# SCH_555_timer_compact_2022-07-11.net
KiCad netlist of a schematic drawn in EasyEDA
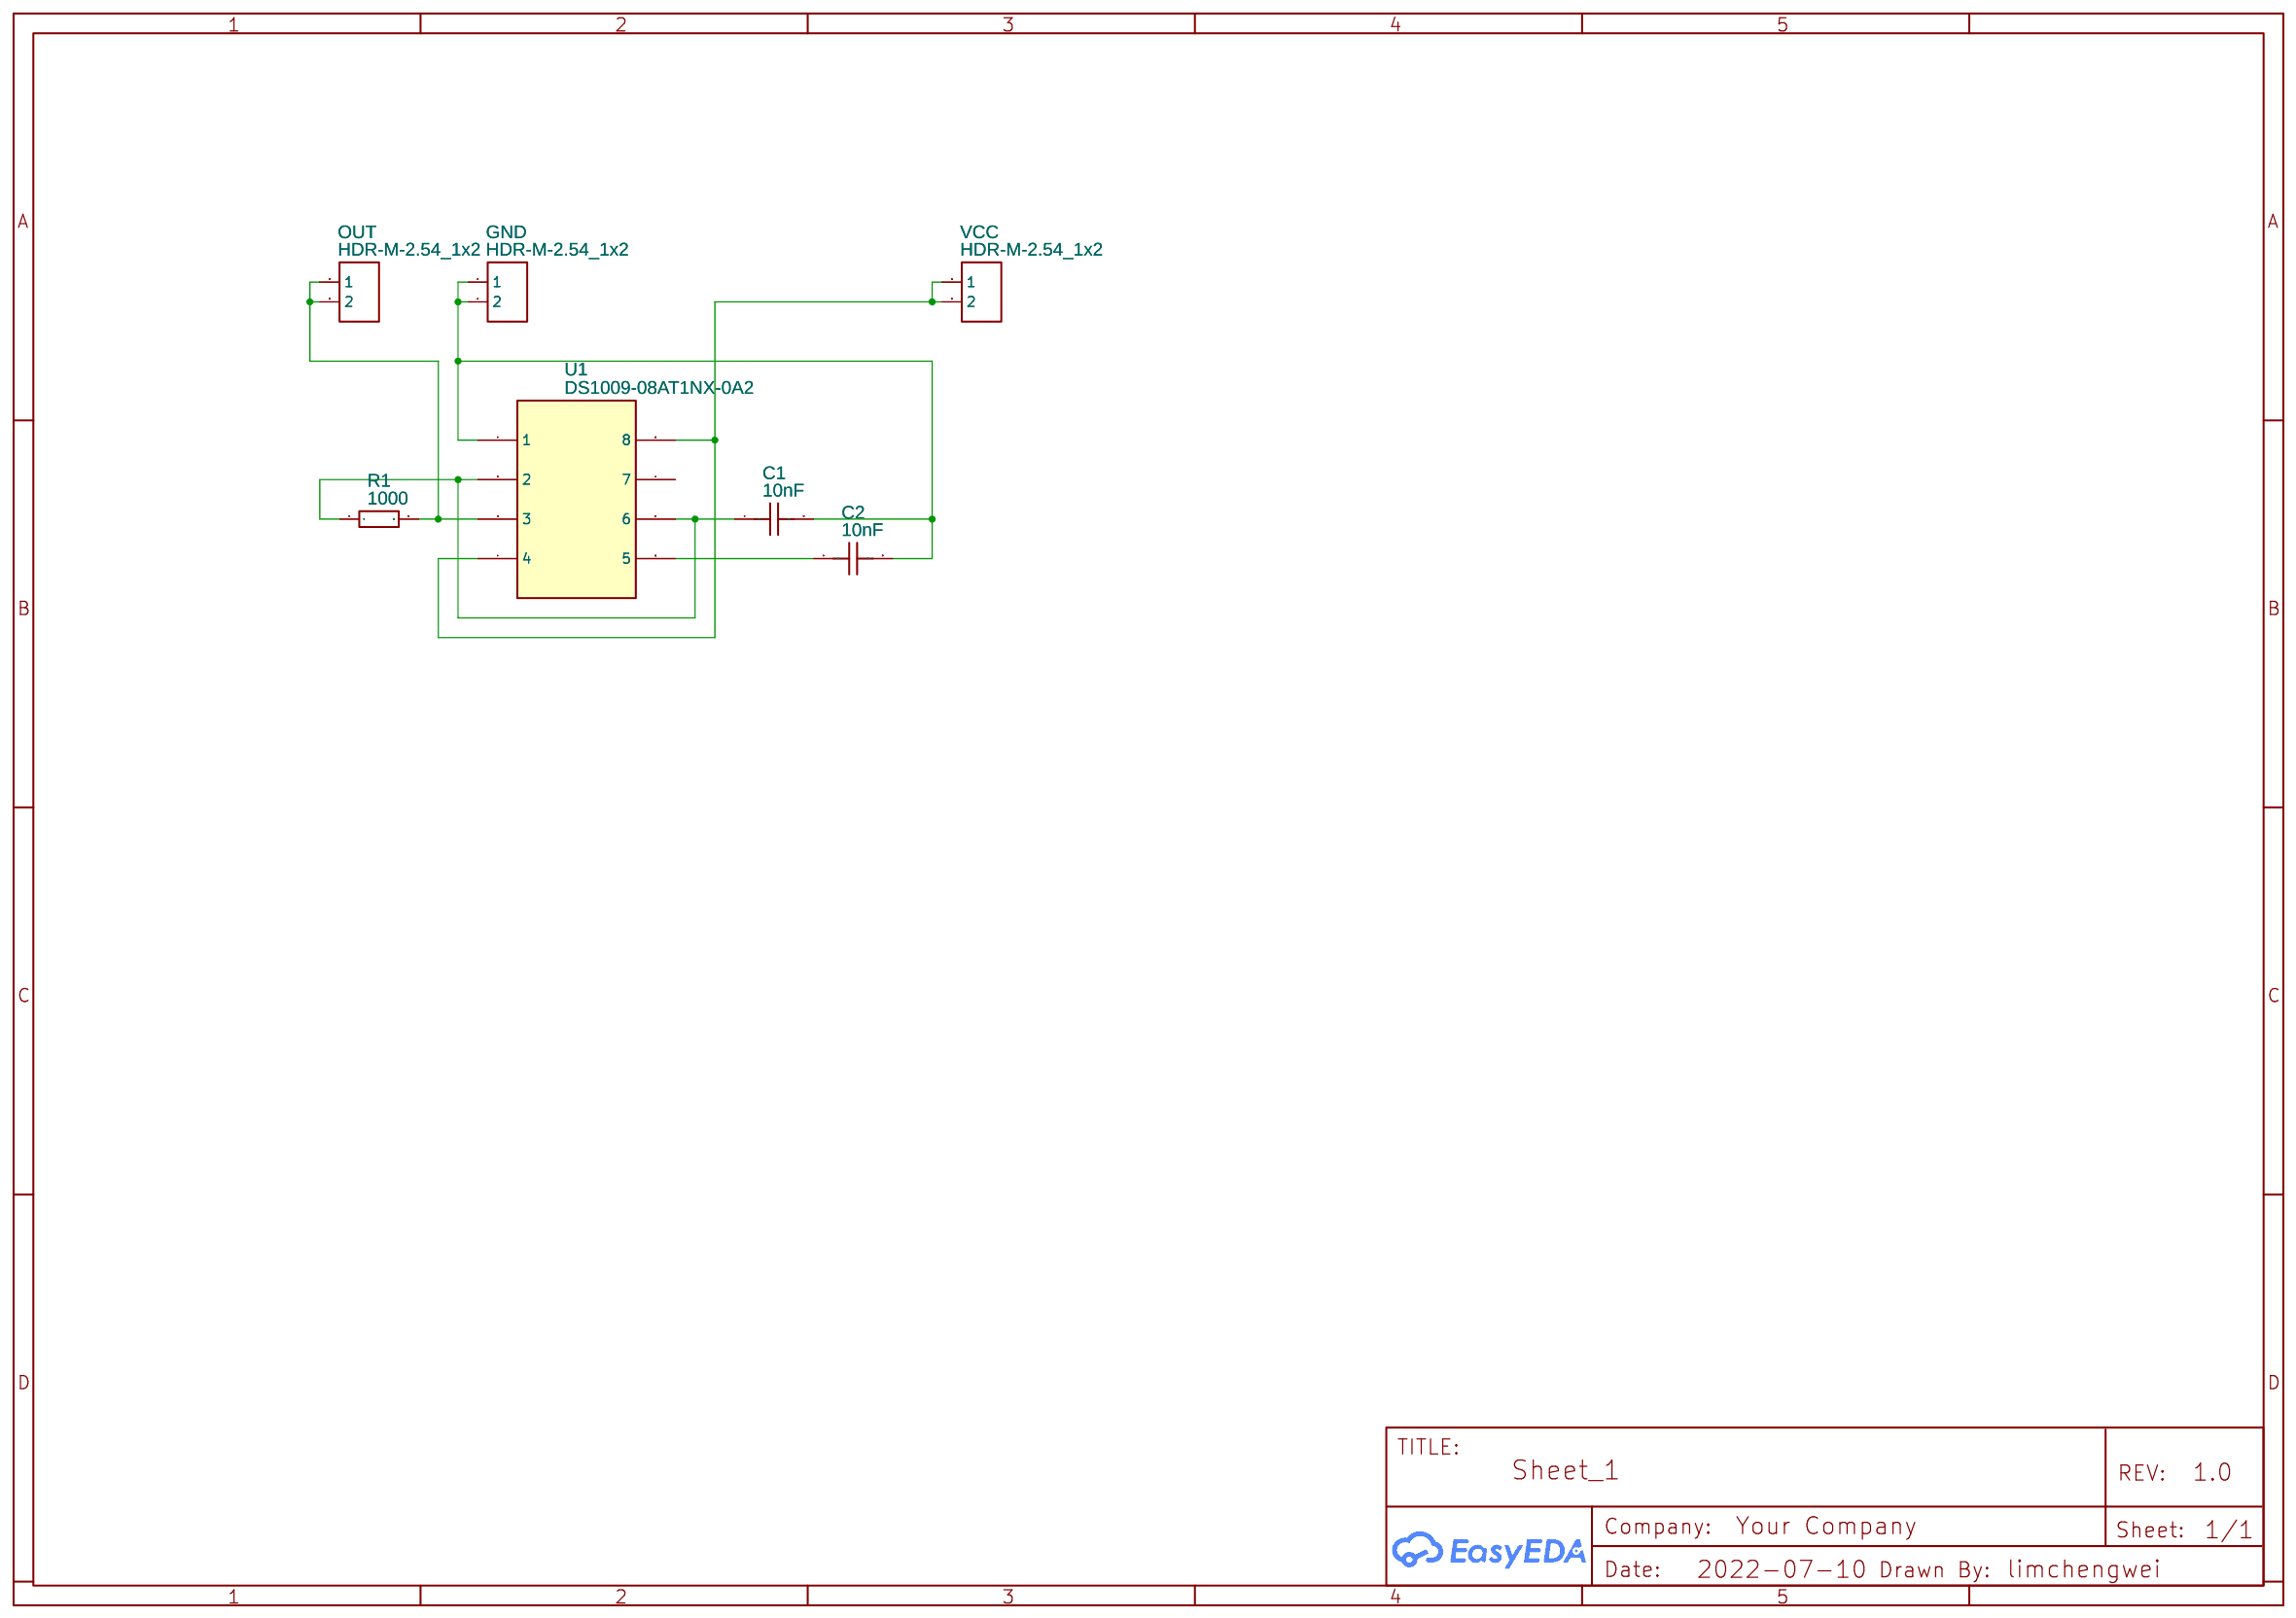
[diagram p0: schematic sheet]

(export (version "E")
  (design (tool "Eeschema 10.0.6"))
  (components
    (comp (ref "C1")
      (value "10nF")
      (fields
        (field (name "BOM_Manufacturer Part") "CC1H103MC76DB45A30S8")
        (field (name "BOM_Supplier Part") "C377837")
      )
      (libsource (lib "") (part "CC1H103MC76DB45A30S8"))
    )
    (comp (ref "C2")
      (value "10nF")
      (fields
        (field (name "BOM_Manufacturer Part") "CC1H103MC76DB45A30S8")
        (field (name "BOM_Supplier Part") "C377837")
      )
      (libsource (lib "") (part "CC1H103MC76DB45A30S8"))
    )
    (comp (ref "GND")
      (value "HDR-M-2.54_1x2")
      (fields (field (name "BOM_Supplier Part") "C124375"))
      (libsource (lib "") (part "HDR-M-2.54_1x2_2"))
    )
    (comp (ref "OUT")
      (value "HDR-M-2.54_1x2")
      (fields (field (name "BOM_Supplier Part") "C124375"))
      (libsource (lib "") (part "HDR-M-2.54_1x2_1"))
    )
    (comp (ref "R1")
      (value "1000")
      (fields (field (name "BOM_Supplier Part") "C119312"))
      (libsource (lib "") (part "MF1/4W-300Ω±1% T52"))
    )
    (comp (ref "U1")
      (value "DS1009-08AT1NX-0A2")
      (fields (field (name "BOM_Supplier Part") "C72124"))
      (libsource (lib "") (part "DS1009-08AT1NX-0A2"))
    )
    (comp (ref "VCC")
      (value "HDR-M-2.54_1x2")
      (fields (field (name "BOM_Supplier Part") "C124375"))
      (libsource (lib "") (part "HDR-M-2.54_1x2"))
    )
  )
  (nets
    (net (code "1") (name "Net-(C1-Pad1)") (class "Default")
      (node (ref "C1") (pin "1") (pinfunction "1_1") (pintype "unspecified"))
      (node (ref "R1") (pin "1") (pinfunction "1_1") (pintype "unspecified"))
      (node (ref "U1") (pin "2") (pinfunction "2_2") (pintype "input"))
      (node (ref "U1") (pin "6") (pinfunction "6_6") (pintype "input"))
    )
    (net (code "2") (name "Net-(C1-Pad2)") (class "Default")
      (node (ref "C1") (pin "2") (pinfunction "2_2") (pintype "unspecified"))
      (node (ref "C2") (pin "2") (pinfunction "2_2") (pintype "unspecified"))
      (node (ref "GND") (pin "1") (pinfunction "1_1") (pintype "unspecified"))
      (node (ref "GND") (pin "2") (pinfunction "2_2") (pintype "unspecified"))
      (node (ref "U1") (pin "1") (pinfunction "1_1") (pintype "input"))
    )
    (net (code "3") (name "Net-(C2-Pad1)") (class "Default")
      (node (ref "C2") (pin "1") (pinfunction "1_1") (pintype "unspecified"))
      (node (ref "U1") (pin "5") (pinfunction "5_5") (pintype "input"))
    )
    (net (code "4") (name "Net-(OUT-Pad1)") (class "Default")
      (node (ref "OUT") (pin "1") (pinfunction "1_1") (pintype "unspecified"))
      (node (ref "OUT") (pin "2") (pinfunction "2_2") (pintype "unspecified"))
      (node (ref "R1") (pin "2") (pinfunction "2_2") (pintype "unspecified"))
      (node (ref "U1") (pin "3") (pinfunction "3_3") (pintype "input"))
    )
    (net (code "5") (name "Net-(U1-Pad4)") (class "Default")
      (node (ref "U1") (pin "4") (pinfunction "4_4") (pintype "input"))
      (node (ref "U1") (pin "8") (pinfunction "8_8") (pintype "input"))
      (node (ref "VCC") (pin "1") (pinfunction "1_1") (pintype "unspecified"))
      (node (ref "VCC") (pin "2") (pinfunction "2_2") (pintype "unspecified"))
    )
    (net (code "6") (name "unconnected-(U1-Pad7)") (class "Default")
      (node (ref "U1") (pin "7") (pinfunction "7_7") (pintype "input"))
    )
  )
)
